# arduinoSPIprog.net
KiCad netlist of a schematic drawn in EAGLE
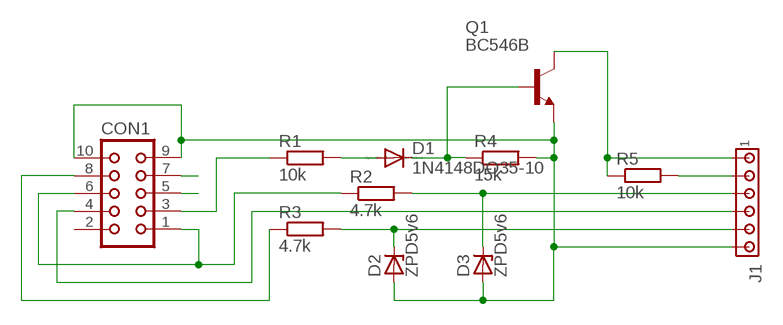
[diagram p0: schematic, sheet 1]

(export (version "E")
  (design (tool "Eeschema 10.0.6"))
  (components
    (comp (ref "CON1")
      (value "CON10")
      (footprint "eagle-import:CON10")
      (libsource (lib "eagle-import") (part "CON10"))
    )
    (comp (ref "D1")
      (value "1N4148DO35-10")
      (footprint "eagle-import:DO35-10")
      (libsource (lib "eagle-import") (part "1N4148DO35-10"))
    )
    (comp (ref "D2")
      (value "ZPD5v6")
      (footprint "eagle-import:DO35Z10")
      (libsource (lib "eagle-import") (part "ZPD"))
    )
    (comp (ref "D3")
      (value "ZPD5v6")
      (footprint "eagle-import:DO35Z10")
      (libsource (lib "eagle-import") (part "ZPD"))
    )
    (comp (ref "J1")
      (value "MTA06-100")
      (footprint "eagle-import:10X06MTA")
      (libsource (lib "eagle-import") (part "MTA06-100"))
    )
    (comp (ref "Q1")
      (value "BC546B")
      (footprint "eagle-import:TO92-EBC")
      (libsource (lib "eagle-import") (part "BC546B"))
    )
    (comp (ref "R1")
      (value "10k")
      (footprint "eagle-import:0207_10")
      (libsource (lib "eagle-import") (part "R-EU_0207/10"))
    )
    (comp (ref "R2")
      (value "4.7k")
      (footprint "eagle-import:0207_10")
      (libsource (lib "eagle-import") (part "R-EU_0207/10"))
    )
    (comp (ref "R3")
      (value "4.7k")
      (footprint "eagle-import:0207_10")
      (libsource (lib "eagle-import") (part "R-EU_0207/10"))
    )
    (comp (ref "R4")
      (value "15k")
      (footprint "eagle-import:0207_10")
      (libsource (lib "eagle-import") (part "R-EU_0207/10"))
    )
    (comp (ref "R5")
      (value "10k")
      (footprint "eagle-import:0207_10")
      (libsource (lib "eagle-import") (part "R-EU_0207/10"))
    )
  )
  (nets
    (net (code "1") (name "Net-(CON1-Pad1)") (class "Default")
      (node (ref "CON1") (pin "1") (pinfunction "1_1") (pintype "passive"))
      (node (ref "CON1") (pin "6") (pinfunction "6_6") (pintype "passive"))
      (node (ref "R2") (pin "1") (pinfunction "1_1") (pintype "passive"))
    )
    (net (code "2") (name "Net-(CON1-Pad3)") (class "Default")
      (node (ref "CON1") (pin "3") (pinfunction "3_3") (pintype "passive"))
      (node (ref "R1") (pin "1") (pinfunction "1_1") (pintype "passive"))
    )
    (net (code "3") (name "Net-(CON1-Pad8)") (class "Default")
      (node (ref "CON1") (pin "8") (pinfunction "8_8") (pintype "passive"))
      (node (ref "R3") (pin "1") (pinfunction "1_1") (pintype "passive"))
    )
    (net (code "4") (name "Net-(D1-PadA)") (class "Default")
      (node (ref "D1") (pin "A") (pinfunction "A_A") (pintype "passive"))
      (node (ref "R1") (pin "2") (pinfunction "2_2") (pintype "passive"))
    )
    (net (code "5") (name "Net-(D1-PadC)") (class "Default")
      (node (ref "D1") (pin "C") (pinfunction "C_C") (pintype "passive"))
      (node (ref "Q1") (pin "B") (pinfunction "B_B") (pintype "passive"))
      (node (ref "R4") (pin "1") (pinfunction "1_1") (pintype "passive"))
    )
    (net (code "6") (name "Net-(J1-1)") (class "Default")
      (node (ref "J1") (pin "6") (pinfunction "1_6") (pintype "passive"))
      (node (ref "Q1") (pin "C") (pinfunction "C_C") (pintype "passive"))
      (node (ref "R5") (pin "1") (pinfunction "1_1") (pintype "passive"))
    )
    (net (code "7") (name "Net-(J1-2)") (class "Default")
      (node (ref "J1") (pin "5") (pinfunction "2_5") (pintype "passive"))
      (node (ref "R5") (pin "2") (pinfunction "2_2") (pintype "passive"))
    )
    (net (code "8") (name "Net-(J1-3)") (class "Default")
      (node (ref "D3") (pin "C") (pinfunction "C_C") (pintype "passive"))
      (node (ref "J1") (pin "4") (pinfunction "3_4") (pintype "passive"))
      (node (ref "R2") (pin "2") (pinfunction "2_2") (pintype "passive"))
    )
    (net (code "9") (name "Net-(J1-4)") (class "Default")
      (node (ref "CON1") (pin "4") (pinfunction "4_4") (pintype "passive"))
      (node (ref "J1") (pin "3") (pinfunction "4_3") (pintype "passive"))
    )
    (net (code "10") (name "Net-(J1-5)") (class "Default")
      (node (ref "D2") (pin "C") (pinfunction "C_C") (pintype "passive"))
      (node (ref "J1") (pin "2") (pinfunction "5_2") (pintype "passive"))
      (node (ref "R3") (pin "2") (pinfunction "2_2") (pintype "passive"))
    )
    (net (code "11") (name "Net-(J1-6)") (class "Default")
      (node (ref "CON1") (pin "10") (pinfunction "10_10") (pintype "passive"))
      (node (ref "CON1") (pin "9") (pinfunction "9_9") (pintype "passive"))
      (node (ref "D2") (pin "A") (pinfunction "A_A") (pintype "passive"))
      (node (ref "D3") (pin "A") (pinfunction "A_A") (pintype "passive"))
      (node (ref "J1") (pin "1") (pinfunction "6_1") (pintype "passive"))
      (node (ref "Q1") (pin "E") (pinfunction "E_E") (pintype "passive"))
      (node (ref "R4") (pin "2") (pinfunction "2_2") (pintype "passive"))
    )
    (net (code "12") (name "unconnected-(CON1-Pad2)") (class "Default")
      (node (ref "CON1") (pin "2") (pinfunction "2_2") (pintype "passive"))
    )
    (net (code "13") (name "unconnected-(CON1-Pad5)") (class "Default")
      (node (ref "CON1") (pin "5") (pinfunction "5_5") (pintype "passive"))
    )
    (net (code "14") (name "unconnected-(CON1-Pad7)") (class "Default")
      (node (ref "CON1") (pin "7") (pinfunction "7_7") (pintype "passive"))
    )
  )
)
